# RangeHood.net
KiCad netlist of a schematic drawn in EAGLE
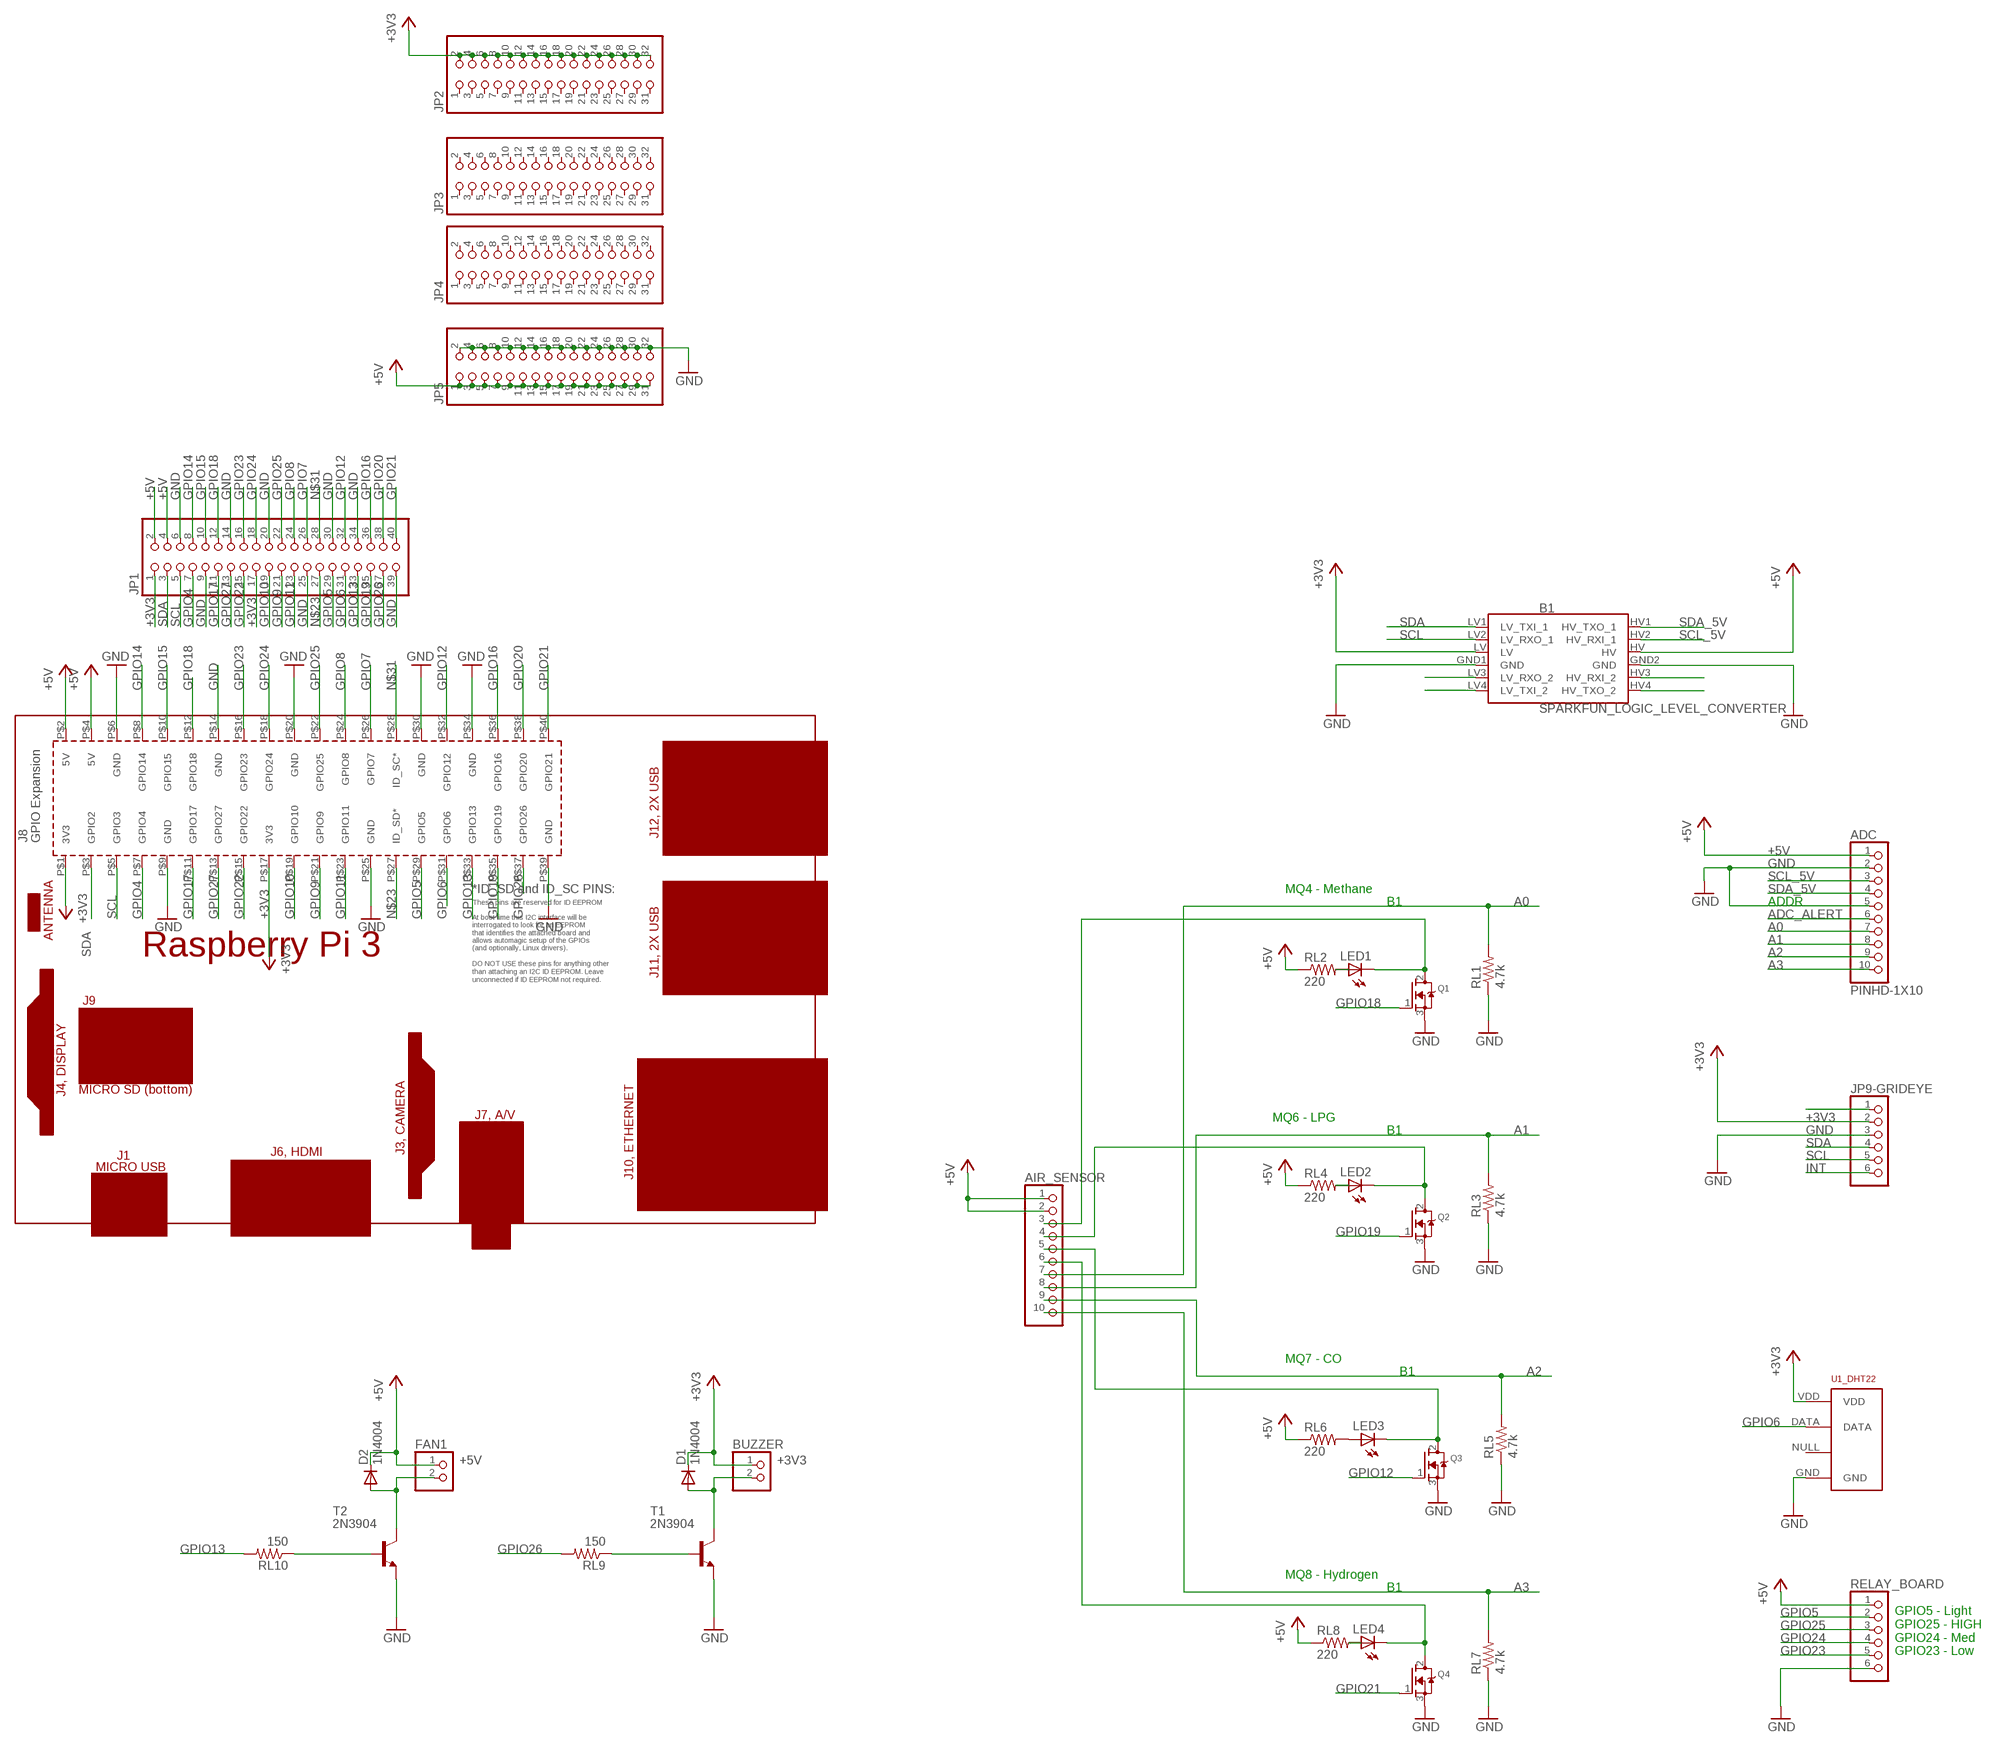
[diagram p0: schematic, sheet 1]

(export (version "E")
  (design (tool "Eeschema 10.0.6"))
  (components
    (comp (ref "ADC")
      (value "PINHD-1X10")
      (footprint "eagle-import:1X10-BIG")
      (libsource (lib "eagle-import") (part "PINHD-1X10"))
    )
    (comp (ref "AIR_SENSOR")
      (value "PINHD-1X10")
      (footprint "eagle-import:1X10")
      (libsource (lib "eagle-import") (part "pinhead_325_PINHD-1X10"))
    )
    (comp (ref "B1")
      (value "SPARKFUN_LOGIC_LEVEL_CONVERTER")
      (footprint "eagle-import:SPARKFUN_LOGIC_LEVEL_CONVERTER")
      (libsource (lib "eagle-import") (part "SPARKFUN_LOGIC_LEVEL_CONVERTER"))
    )
    (comp (ref "BUZZER")
      (value "PINHD-1X2")
      (footprint "eagle-import:1X02")
      (libsource (lib "eagle-import") (part "PINHD-1X2"))
    )
    (comp (ref "D1")
      (value "1N4004")
      (footprint "eagle-import:DO41-10")
      (libsource (lib "eagle-import") (part "1N4004"))
    )
    (comp (ref "D2")
      (value "1N4004")
      (footprint "eagle-import:DO41-10")
      (libsource (lib "eagle-import") (part "1N4004"))
    )
    (comp (ref "FAN1")
      (value "PINHD-1X2")
      (footprint "eagle-import:1X02")
      (libsource (lib "eagle-import") (part "PINHD-1X2"))
    )
    (comp (ref "JP1")
      (value "PINHD-2X20")
      (footprint "eagle-import:2X20")
      (libsource (lib "eagle-import") (part "PINHD-2X20"))
    )
    (comp (ref "JP2")
      (value "PINHD-2X16")
      (footprint "eagle-import:2X16")
      (libsource (lib "eagle-import") (part "PINHD-2X16"))
    )
    (comp (ref "JP3")
      (value "PINHD-2X16")
      (footprint "eagle-import:2X16")
      (libsource (lib "eagle-import") (part "PINHD-2X16"))
    )
    (comp (ref "JP4")
      (value "PINHD-2X16")
      (footprint "eagle-import:2X16")
      (libsource (lib "eagle-import") (part "PINHD-2X16"))
    )
    (comp (ref "JP5")
      (value "PINHD-2X16")
      (footprint "eagle-import:2X16")
      (libsource (lib "eagle-import") (part "PINHD-2X16"))
    )
    (comp (ref "JP9-GRIDEYE")
      (value "PINHD-1X6")
      (footprint "eagle-import:1X06")
      (libsource (lib "eagle-import") (part "PINHD-1X6"))
    )
    (comp (ref "LED1")
      (value "LED3MM")
      (footprint "eagle-import:LED3MM")
      (libsource (lib "eagle-import") (part "LED3MM"))
    )
    (comp (ref "LED2")
      (value "LED3MM")
      (footprint "eagle-import:LED3MM")
      (libsource (lib "eagle-import") (part "LED3MM"))
    )
    (comp (ref "LED3")
      (value "LED3MM")
      (footprint "eagle-import:LED3MM")
      (libsource (lib "eagle-import") (part "LED3MM"))
    )
    (comp (ref "LED4")
      (value "LED3MM")
      (footprint "eagle-import:LED3MM")
      (libsource (lib "eagle-import") (part "LED3MM"))
    )
    (comp (ref "PCB1")
      (value "RPI3")
      (footprint "eagle-import:RPI3")
      (libsource (lib "eagle-import") (part "RPI3"))
    )
    (comp (ref "Q1")
      (value "MOSFET-NGDS_TO220V")
      (footprint "eagle-import:TO220V")
      (libsource (lib "eagle-import") (part "MOSFET-NGDS_TO220V"))
    )
    (comp (ref "Q2")
      (value "MOSFET-NGDS_TO220V")
      (footprint "eagle-import:TO220V")
      (libsource (lib "eagle-import") (part "MOSFET-NGDS_TO220V"))
    )
    (comp (ref "Q3")
      (value "MOSFET-NGDS_TO220V")
      (footprint "eagle-import:TO220V")
      (libsource (lib "eagle-import") (part "MOSFET-NGDS_TO220V"))
    )
    (comp (ref "Q4")
      (value "MOSFET-NGDS_TO220V")
      (footprint "eagle-import:TO220V")
      (libsource (lib "eagle-import") (part "MOSFET-NGDS_TO220V"))
    )
    (comp (ref "RELAY_BOARD")
      (value "PINHD-1X6")
      (footprint "eagle-import:1X06")
      (libsource (lib "eagle-import") (part "PINHD-1X6"))
    )
    (comp (ref "RL1")
      (value "4.7k")
      (footprint "eagle-import:M0805")
      (libsource (lib "eagle-import") (part "R-US_M0805"))
    )
    (comp (ref "RL2")
      (value "220")
      (footprint "eagle-import:M0805")
      (libsource (lib "eagle-import") (part "R-US_M0805"))
    )
    (comp (ref "RL3")
      (value "4.7k")
      (footprint "eagle-import:M0805")
      (libsource (lib "eagle-import") (part "R-US_M0805"))
    )
    (comp (ref "RL4")
      (value "220")
      (footprint "eagle-import:M0805")
      (libsource (lib "eagle-import") (part "R-US_M0805"))
    )
    (comp (ref "RL5")
      (value "4.7k")
      (footprint "eagle-import:M0805")
      (libsource (lib "eagle-import") (part "R-US_M0805"))
    )
    (comp (ref "RL6")
      (value "220")
      (footprint "eagle-import:M0805")
      (libsource (lib "eagle-import") (part "R-US_M0805"))
    )
    (comp (ref "RL7")
      (value "4.7k")
      (footprint "eagle-import:M0805")
      (libsource (lib "eagle-import") (part "R-US_M0805"))
    )
    (comp (ref "RL8")
      (value "220")
      (footprint "eagle-import:M0805")
      (libsource (lib "eagle-import") (part "R-US_M0805"))
    )
    (comp (ref "RL9")
      (value "150")
      (footprint "eagle-import:M0805")
      (libsource (lib "eagle-import") (part "R-US_M0805"))
    )
    (comp (ref "RL10")
      (value "150")
      (footprint "eagle-import:M0805")
      (libsource (lib "eagle-import") (part "R-US_M0805"))
    )
    (comp (ref "T1")
      (value "2N3904")
      (footprint "eagle-import:TO92")
      (libsource (lib "eagle-import") (part "2N3904"))
    )
    (comp (ref "T2")
      (value "2N3904")
      (footprint "eagle-import:TO92")
      (libsource (lib "eagle-import") (part "2N3904"))
    )
    (comp (ref "U1_DHT22")
      (value "RHT03_DHT-22_AM2302")
      (footprint "eagle-import:RHT03_DHT-22")
      (libsource (lib "eagle-import") (part "RHT03_DHT-22_AM2302"))
    )
  )
  (nets
    (net (code "1") (name "+3V3") (class "Default")
      (node (ref "B1") (pin "LV") (pinfunction "LV_LV") (pintype "power_in"))
      (node (ref "BUZZER") (pin "1") (pinfunction "1_1") (pintype "passive"))
      (node (ref "D1") (pin "C") (pinfunction "C_C") (pintype "passive"))
      (node (ref "JP1") (pin "1") (pinfunction "1_1") (pintype "passive"))
      (node (ref "JP1") (pin "17") (pinfunction "17_17") (pintype "passive"))
      (node (ref "JP2") (pin "10") (pinfunction "10_10") (pintype "passive"))
      (node (ref "JP2") (pin "12") (pinfunction "12_12") (pintype "passive"))
      (node (ref "JP2") (pin "14") (pinfunction "14_14") (pintype "passive"))
      (node (ref "JP2") (pin "16") (pinfunction "16_16") (pintype "passive"))
      (node (ref "JP2") (pin "18") (pinfunction "18_18") (pintype "passive"))
      (node (ref "JP2") (pin "2") (pinfunction "2_2") (pintype "passive"))
      (node (ref "JP2") (pin "20") (pinfunction "20_20") (pintype "passive"))
      (node (ref "JP2") (pin "22") (pinfunction "22_22") (pintype "passive"))
      (node (ref "JP2") (pin "24") (pinfunction "24_24") (pintype "passive"))
      (node (ref "JP2") (pin "26") (pinfunction "26_26") (pintype "passive"))
      (node (ref "JP2") (pin "28") (pinfunction "28_28") (pintype "passive"))
      (node (ref "JP2") (pin "30") (pinfunction "30_30") (pintype "passive"))
      (node (ref "JP2") (pin "32") (pinfunction "32_32") (pintype "passive"))
      (node (ref "JP2") (pin "4") (pinfunction "4_4") (pintype "passive"))
      (node (ref "JP2") (pin "6") (pinfunction "6_6") (pintype "passive"))
      (node (ref "JP2") (pin "8") (pinfunction "8_8") (pintype "passive"))
      (node (ref "JP9-GRIDEYE") (pin "2") (pinfunction "2_2") (pintype "passive"))
      (node (ref "PCB1") (pin "P$1") (pinfunction "3V3_P$1") (pintype "bidirectional"))
      (node (ref "PCB1") (pin "P$17") (pinfunction "3V3_P$17") (pintype "bidirectional"))
      (node (ref "U1_DHT22") (pin "VDD") (pinfunction "VDD_VDD") (pintype "power_in"))
    )
    (net (code "2") (name "+5V") (class "Default")
      (node (ref "ADC") (pin "1") (pinfunction "1_1") (pintype "passive"))
      (node (ref "AIR_SENSOR") (pin "1") (pinfunction "1_1") (pintype "passive"))
      (node (ref "AIR_SENSOR") (pin "2") (pinfunction "2_2") (pintype "passive"))
      (node (ref "B1") (pin "HV") (pinfunction "HV_HV") (pintype "power_in"))
      (node (ref "D2") (pin "C") (pinfunction "C_C") (pintype "passive"))
      (node (ref "FAN1") (pin "1") (pinfunction "1_1") (pintype "passive"))
      (node (ref "JP1") (pin "2") (pinfunction "2_2") (pintype "passive"))
      (node (ref "JP1") (pin "4") (pinfunction "4_4") (pintype "passive"))
      (node (ref "JP5") (pin "1") (pinfunction "1_1") (pintype "passive"))
      (node (ref "JP5") (pin "11") (pinfunction "11_11") (pintype "passive"))
      (node (ref "JP5") (pin "13") (pinfunction "13_13") (pintype "passive"))
      (node (ref "JP5") (pin "15") (pinfunction "15_15") (pintype "passive"))
      (node (ref "JP5") (pin "17") (pinfunction "17_17") (pintype "passive"))
      (node (ref "JP5") (pin "19") (pinfunction "19_19") (pintype "passive"))
      (node (ref "JP5") (pin "21") (pinfunction "21_21") (pintype "passive"))
      (node (ref "JP5") (pin "23") (pinfunction "23_23") (pintype "passive"))
      (node (ref "JP5") (pin "25") (pinfunction "25_25") (pintype "passive"))
      (node (ref "JP5") (pin "27") (pinfunction "27_27") (pintype "passive"))
      (node (ref "JP5") (pin "29") (pinfunction "29_29") (pintype "passive"))
      (node (ref "JP5") (pin "3") (pinfunction "3_3") (pintype "passive"))
      (node (ref "JP5") (pin "31") (pinfunction "31_31") (pintype "passive"))
      (node (ref "JP5") (pin "5") (pinfunction "5_5") (pintype "passive"))
      (node (ref "JP5") (pin "7") (pinfunction "7_7") (pintype "passive"))
      (node (ref "JP5") (pin "9") (pinfunction "9_9") (pintype "passive"))
      (node (ref "PCB1") (pin "P$2") (pinfunction "5V_P$2") (pintype "bidirectional"))
      (node (ref "PCB1") (pin "P$4") (pinfunction "5V_P$4") (pintype "bidirectional"))
      (node (ref "RELAY_BOARD") (pin "1") (pinfunction "1_1") (pintype "passive"))
      (node (ref "RL2") (pin "1") (pinfunction "1_1") (pintype "passive"))
      (node (ref "RL4") (pin "1") (pinfunction "1_1") (pintype "passive"))
      (node (ref "RL6") (pin "1") (pinfunction "1_1") (pintype "passive"))
      (node (ref "RL8") (pin "1") (pinfunction "1_1") (pintype "passive"))
    )
    (net (code "3") (name "A0") (class "Default")
      (node (ref "ADC") (pin "7") (pinfunction "7_7") (pintype "passive"))
      (node (ref "AIR_SENSOR") (pin "7") (pinfunction "7_7") (pintype "passive"))
      (node (ref "RL1") (pin "2") (pinfunction "2_2") (pintype "passive"))
    )
    (net (code "4") (name "A1") (class "Default")
      (node (ref "ADC") (pin "8") (pinfunction "8_8") (pintype "passive"))
      (node (ref "AIR_SENSOR") (pin "8") (pinfunction "8_8") (pintype "passive"))
      (node (ref "RL3") (pin "2") (pinfunction "2_2") (pintype "passive"))
    )
    (net (code "5") (name "A2") (class "Default")
      (node (ref "ADC") (pin "9") (pinfunction "9_9") (pintype "passive"))
      (node (ref "AIR_SENSOR") (pin "9") (pinfunction "9_9") (pintype "passive"))
      (node (ref "RL5") (pin "2") (pinfunction "2_2") (pintype "passive"))
    )
    (net (code "6") (name "A3") (class "Default")
      (node (ref "ADC") (pin "10") (pinfunction "10_10") (pintype "passive"))
      (node (ref "AIR_SENSOR") (pin "10") (pinfunction "10_10") (pintype "passive"))
      (node (ref "RL7") (pin "2") (pinfunction "2_2") (pintype "passive"))
    )
    (net (code "7") (name "ADC_ALERT") (class "Default")
      (node (ref "ADC") (pin "6") (pinfunction "6_6") (pintype "passive"))
    )
    (net (code "8") (name "GND") (class "Default")
      (node (ref "ADC") (pin "2") (pinfunction "2_2") (pintype "passive"))
      (node (ref "ADC") (pin "5") (pinfunction "5_5") (pintype "passive"))
      (node (ref "B1") (pin "GND1") (pinfunction "GND_GND1") (pintype "power_in"))
      (node (ref "B1") (pin "GND2") (pinfunction "GND_GND2") (pintype "power_in"))
      (node (ref "JP1") (pin "14") (pinfunction "14_14") (pintype "passive"))
      (node (ref "JP1") (pin "20") (pinfunction "20_20") (pintype "passive"))
      (node (ref "JP1") (pin "25") (pinfunction "25_25") (pintype "passive"))
      (node (ref "JP1") (pin "30") (pinfunction "30_30") (pintype "passive"))
      (node (ref "JP1") (pin "34") (pinfunction "34_34") (pintype "passive"))
      (node (ref "JP1") (pin "39") (pinfunction "39_39") (pintype "passive"))
      (node (ref "JP1") (pin "6") (pinfunction "6_6") (pintype "passive"))
      (node (ref "JP1") (pin "9") (pinfunction "9_9") (pintype "passive"))
      (node (ref "JP5") (pin "10") (pinfunction "10_10") (pintype "passive"))
      (node (ref "JP5") (pin "12") (pinfunction "12_12") (pintype "passive"))
      (node (ref "JP5") (pin "14") (pinfunction "14_14") (pintype "passive"))
      (node (ref "JP5") (pin "16") (pinfunction "16_16") (pintype "passive"))
      (node (ref "JP5") (pin "18") (pinfunction "18_18") (pintype "passive"))
      (node (ref "JP5") (pin "2") (pinfunction "2_2") (pintype "passive"))
      (node (ref "JP5") (pin "20") (pinfunction "20_20") (pintype "passive"))
      (node (ref "JP5") (pin "22") (pinfunction "22_22") (pintype "passive"))
      (node (ref "JP5") (pin "24") (pinfunction "24_24") (pintype "passive"))
      (node (ref "JP5") (pin "26") (pinfunction "26_26") (pintype "passive"))
      (node (ref "JP5") (pin "28") (pinfunction "28_28") (pintype "passive"))
      (node (ref "JP5") (pin "30") (pinfunction "30_30") (pintype "passive"))
      (node (ref "JP5") (pin "32") (pinfunction "32_32") (pintype "passive"))
      (node (ref "JP5") (pin "4") (pinfunction "4_4") (pintype "passive"))
      (node (ref "JP5") (pin "6") (pinfunction "6_6") (pintype "passive"))
      (node (ref "JP5") (pin "8") (pinfunction "8_8") (pintype "passive"))
      (node (ref "JP9-GRIDEYE") (pin "3") (pinfunction "3_3") (pintype "passive"))
      (node (ref "PCB1") (pin "P$14") (pinfunction "GND_P$14") (pintype "bidirectional"))
      (node (ref "PCB1") (pin "P$20") (pinfunction "GND_P$20") (pintype "bidirectional"))
      (node (ref "PCB1") (pin "P$25") (pinfunction "GND_P$25") (pintype "bidirectional"))
      (node (ref "PCB1") (pin "P$30") (pinfunction "GND_P$30") (pintype "bidirectional"))
      (node (ref "PCB1") (pin "P$34") (pinfunction "GND_P$34") (pintype "bidirectional"))
      (node (ref "PCB1") (pin "P$39") (pinfunction "GND_P$39") (pintype "bidirectional"))
      (node (ref "PCB1") (pin "P$6") (pinfunction "GND_P$6") (pintype "bidirectional"))
      (node (ref "PCB1") (pin "P$9") (pinfunction "GND_P$9") (pintype "bidirectional"))
      (node (ref "Q1") (pin "3") (pinfunction "S_3") (pintype "bidirectional"))
      (node (ref "Q2") (pin "3") (pinfunction "S_3") (pintype "bidirectional"))
      (node (ref "Q3") (pin "3") (pinfunction "S_3") (pintype "bidirectional"))
      (node (ref "Q4") (pin "3") (pinfunction "S_3") (pintype "bidirectional"))
      (node (ref "RELAY_BOARD") (pin "6") (pinfunction "6_6") (pintype "passive"))
      (node (ref "RL1") (pin "1") (pinfunction "1_1") (pintype "passive"))
      (node (ref "RL3") (pin "1") (pinfunction "1_1") (pintype "passive"))
      (node (ref "RL5") (pin "1") (pinfunction "1_1") (pintype "passive"))
      (node (ref "RL7") (pin "1") (pinfunction "1_1") (pintype "passive"))
      (node (ref "T1") (pin "3") (pinfunction "E_3") (pintype "passive"))
      (node (ref "T2") (pin "3") (pinfunction "E_3") (pintype "passive"))
      (node (ref "U1_DHT22") (pin "GND") (pinfunction "GND_GND") (pintype "power_in"))
    )
    (net (code "9") (name "GPIO4") (class "Default")
      (node (ref "JP1") (pin "7") (pinfunction "7_7") (pintype "passive"))
      (node (ref "PCB1") (pin "P$7") (pinfunction "GPIO4_P$7") (pintype "bidirectional"))
    )
    (net (code "10") (name "GPIO5") (class "Default")
      (node (ref "JP1") (pin "29") (pinfunction "29_29") (pintype "passive"))
      (node (ref "PCB1") (pin "P$29") (pinfunction "GPIO5_P$29") (pintype "bidirectional"))
      (node (ref "RELAY_BOARD") (pin "2") (pinfunction "2_2") (pintype "passive"))
    )
    (net (code "11") (name "GPIO6") (class "Default")
      (node (ref "JP1") (pin "31") (pinfunction "31_31") (pintype "passive"))
      (node (ref "PCB1") (pin "P$31") (pinfunction "GPIO6_P$31") (pintype "bidirectional"))
      (node (ref "U1_DHT22") (pin "DATA") (pinfunction "DATA_DATA") (pintype "bidirectional"))
    )
    (net (code "12") (name "GPIO7") (class "Default")
      (node (ref "JP1") (pin "26") (pinfunction "26_26") (pintype "passive"))
      (node (ref "PCB1") (pin "P$26") (pinfunction "GPIO7_P$26") (pintype "bidirectional"))
    )
    (net (code "13") (name "GPIO8") (class "Default")
      (node (ref "JP1") (pin "24") (pinfunction "24_24") (pintype "passive"))
      (node (ref "PCB1") (pin "P$24") (pinfunction "GPIO8_P$24") (pintype "bidirectional"))
    )
    (net (code "14") (name "GPIO9") (class "Default")
      (node (ref "JP1") (pin "21") (pinfunction "21_21") (pintype "passive"))
      (node (ref "PCB1") (pin "P$21") (pinfunction "GPIO9_P$21") (pintype "bidirectional"))
    )
    (net (code "15") (name "GPIO10") (class "Default")
      (node (ref "JP1") (pin "19") (pinfunction "19_19") (pintype "passive"))
      (node (ref "PCB1") (pin "P$19") (pinfunction "GPIO10_P$19") (pintype "bidirectional"))
    )
    (net (code "16") (name "GPIO11") (class "Default")
      (node (ref "JP1") (pin "23") (pinfunction "23_23") (pintype "passive"))
      (node (ref "PCB1") (pin "P$23") (pinfunction "GPIO11_P$23") (pintype "bidirectional"))
    )
    (net (code "17") (name "GPIO12") (class "Default")
      (node (ref "JP1") (pin "32") (pinfunction "32_32") (pintype "passive"))
      (node (ref "PCB1") (pin "P$32") (pinfunction "GPIO12_P$32") (pintype "bidirectional"))
      (node (ref "Q3") (pin "1") (pinfunction "G_1") (pintype "bidirectional"))
    )
    (net (code "18") (name "GPIO13") (class "Default")
      (node (ref "JP1") (pin "33") (pinfunction "33_33") (pintype "passive"))
      (node (ref "PCB1") (pin "P$33") (pinfunction "GPIO13_P$33") (pintype "bidirectional"))
      (node (ref "RL10") (pin "2") (pinfunction "2_2") (pintype "passive"))
    )
    (net (code "19") (name "GPIO14") (class "Default")
      (node (ref "JP1") (pin "8") (pinfunction "8_8") (pintype "passive"))
      (node (ref "PCB1") (pin "P$8") (pinfunction "GPIO14_P$8") (pintype "bidirectional"))
    )
    (net (code "20") (name "GPIO15") (class "Default")
      (node (ref "JP1") (pin "10") (pinfunction "10_10") (pintype "passive"))
      (node (ref "PCB1") (pin "P$10") (pinfunction "GPIO15_P$10") (pintype "bidirectional"))
    )
    (net (code "21") (name "GPIO16") (class "Default")
      (node (ref "JP1") (pin "36") (pinfunction "36_36") (pintype "passive"))
      (node (ref "PCB1") (pin "P$36") (pinfunction "GPIO16_P$36") (pintype "bidirectional"))
    )
    (net (code "22") (name "GPIO17") (class "Default")
      (node (ref "JP1") (pin "11") (pinfunction "11_11") (pintype "passive"))
      (node (ref "PCB1") (pin "P$11") (pinfunction "GPIO17_P$11") (pintype "bidirectional"))
    )
    (net (code "23") (name "GPIO18") (class "Default")
      (node (ref "JP1") (pin "12") (pinfunction "12_12") (pintype "passive"))
      (node (ref "PCB1") (pin "P$12") (pinfunction "GPIO18_P$12") (pintype "bidirectional"))
      (node (ref "Q1") (pin "1") (pinfunction "G_1") (pintype "bidirectional"))
    )
    (net (code "24") (name "GPIO19") (class "Default")
      (node (ref "JP1") (pin "35") (pinfunction "35_35") (pintype "passive"))
      (node (ref "PCB1") (pin "P$35") (pinfunction "GPIO19_P$35") (pintype "bidirectional"))
      (node (ref "Q2") (pin "1") (pinfunction "G_1") (pintype "bidirectional"))
    )
    (net (code "25") (name "GPIO20") (class "Default")
      (node (ref "JP1") (pin "38") (pinfunction "38_38") (pintype "passive"))
      (node (ref "PCB1") (pin "P$38") (pinfunction "GPIO20_P$38") (pintype "bidirectional"))
    )
    (net (code "26") (name "GPIO21") (class "Default")
      (node (ref "JP1") (pin "40") (pinfunction "40_40") (pintype "passive"))
      (node (ref "PCB1") (pin "P$40") (pinfunction "GPIO21_P$40") (pintype "bidirectional"))
      (node (ref "Q4") (pin "1") (pinfunction "G_1") (pintype "bidirectional"))
    )
    (net (code "27") (name "GPIO22") (class "Default")
      (node (ref "JP1") (pin "15") (pinfunction "15_15") (pintype "passive"))
      (node (ref "PCB1") (pin "P$15") (pinfunction "GPIO22_P$15") (pintype "bidirectional"))
    )
    (net (code "28") (name "GPIO23") (class "Default")
      (node (ref "JP1") (pin "16") (pinfunction "16_16") (pintype "passive"))
      (node (ref "PCB1") (pin "P$16") (pinfunction "GPIO23_P$16") (pintype "bidirectional"))
      (node (ref "RELAY_BOARD") (pin "5") (pinfunction "5_5") (pintype "passive"))
    )
    (net (code "29") (name "GPIO24") (class "Default")
      (node (ref "JP1") (pin "18") (pinfunction "18_18") (pintype "passive"))
      (node (ref "PCB1") (pin "P$18") (pinfunction "GPIO24_P$18") (pintype "bidirectional"))
      (node (ref "RELAY_BOARD") (pin "4") (pinfunction "4_4") (pintype "passive"))
    )
    (net (code "30") (name "GPIO25") (class "Default")
      (node (ref "JP1") (pin "22") (pinfunction "22_22") (pintype "passive"))
      (node (ref "PCB1") (pin "P$22") (pinfunction "GPIO25_P$22") (pintype "bidirectional"))
      (node (ref "RELAY_BOARD") (pin "3") (pinfunction "3_3") (pintype "passive"))
    )
    (net (code "31") (name "GPIO26") (class "Default")
      (node (ref "JP1") (pin "37") (pinfunction "37_37") (pintype "passive"))
      (node (ref "PCB1") (pin "P$37") (pinfunction "GPIO26_P$37") (pintype "bidirectional"))
      (node (ref "RL9") (pin "2") (pinfunction "2_2") (pintype "passive"))
    )
    (net (code "32") (name "GPIO27") (class "Default")
      (node (ref "JP1") (pin "13") (pinfunction "13_13") (pintype "passive"))
      (node (ref "PCB1") (pin "P$13") (pinfunction "GPIO27_P$13") (pintype "bidirectional"))
    )
    (net (code "33") (name "INT") (class "Default")
      (node (ref "JP9-GRIDEYE") (pin "6") (pinfunction "6_6") (pintype "passive"))
    )
    (net (code "34") (name "N$23") (class "Default")
      (node (ref "JP1") (pin "27") (pinfunction "27_27") (pintype "passive"))
      (node (ref "PCB1") (pin "P$27") (pinfunction "ID_SD*_P$27") (pintype "bidirectional"))
    )
    (net (code "35") (name "N$31") (class "Default")
      (node (ref "JP1") (pin "28") (pinfunction "28_28") (pintype "passive"))
      (node (ref "PCB1") (pin "P$28") (pinfunction "ID_SC*_P$28") (pintype "bidirectional"))
    )
    (net (code "36") (name "Net-(LED1-C)") (class "Default")
      (node (ref "AIR_SENSOR") (pin "3") (pinfunction "3_3") (pintype "passive"))
      (node (ref "LED1") (pin "K") (pinfunction "C_K") (pintype "passive"))
      (node (ref "Q1") (pin "2") (pinfunction "D_2") (pintype "bidirectional"))
    )
    (net (code "37") (name "Net-(LED1-PadA)") (class "Default")
      (node (ref "LED1") (pin "A") (pinfunction "A_A") (pintype "passive"))
      (node (ref "RL2") (pin "2") (pinfunction "2_2") (pintype "passive"))
    )
    (net (code "38") (name "Net-(LED2-C)") (class "Default")
      (node (ref "AIR_SENSOR") (pin "4") (pinfunction "4_4") (pintype "passive"))
      (node (ref "LED2") (pin "K") (pinfunction "C_K") (pintype "passive"))
      (node (ref "Q2") (pin "2") (pinfunction "D_2") (pintype "bidirectional"))
    )
    (net (code "39") (name "Net-(LED2-PadA)") (class "Default")
      (node (ref "LED2") (pin "A") (pinfunction "A_A") (pintype "passive"))
      (node (ref "RL4") (pin "2") (pinfunction "2_2") (pintype "passive"))
    )
    (net (code "40") (name "Net-(LED3-C)") (class "Default")
      (node (ref "AIR_SENSOR") (pin "5") (pinfunction "5_5") (pintype "passive"))
      (node (ref "LED3") (pin "K") (pinfunction "C_K") (pintype "passive"))
      (node (ref "Q3") (pin "2") (pinfunction "D_2") (pintype "bidirectional"))
    )
    (net (code "41") (name "Net-(LED3-PadA)") (class "Default")
      (node (ref "LED3") (pin "A") (pinfunction "A_A") (pintype "passive"))
      (node (ref "RL6") (pin "2") (pinfunction "2_2") (pintype "passive"))
    )
    (net (code "42") (name "Net-(LED4-C)") (class "Default")
      (node (ref "AIR_SENSOR") (pin "6") (pinfunction "6_6") (pintype "passive"))
      (node (ref "LED4") (pin "K") (pinfunction "C_K") (pintype "passive"))
      (node (ref "Q4") (pin "2") (pinfunction "D_2") (pintype "bidirectional"))
    )
    (net (code "43") (name "Net-(LED4-PadA)") (class "Default")
      (node (ref "LED4") (pin "A") (pinfunction "A_A") (pintype "passive"))
      (node (ref "RL8") (pin "2") (pinfunction "2_2") (pintype "passive"))
    )
    (net (code "44") (name "Net-(T1-B)") (class "Default")
      (node (ref "RL9") (pin "1") (pinfunction "1_1") (pintype "passive"))
      (node (ref "T1") (pin "2") (pinfunction "B_2") (pintype "passive"))
    )
    (net (code "45") (name "Net-(T1-C)") (class "Default")
      (node (ref "BUZZER") (pin "2") (pinfunction "2_2") (pintype "passive"))
      (node (ref "D1") (pin "A") (pinfunction "A_A") (pintype "passive"))
      (node (ref "T1") (pin "1") (pinfunction "C_1") (pintype "passive"))
    )
    (net (code "46") (name "Net-(T2-B)") (class "Default")
      (node (ref "RL10") (pin "1") (pinfunction "1_1") (pintype "passive"))
      (node (ref "T2") (pin "2") (pinfunction "B_2") (pintype "passive"))
    )
    (net (code "47") (name "Net-(T2-C)") (class "Default")
      (node (ref "D2") (pin "A") (pinfunction "A_A") (pintype "passive"))
      (node (ref "FAN1") (pin "2") (pinfunction "2_2") (pintype "passive"))
      (node (ref "T2") (pin "1") (pinfunction "C_1") (pintype "passive"))
    )
    (net (code "48") (name "SCL") (class "Default")
      (node (ref "B1") (pin "LV2") (pinfunction "LV_RXO_1_LV2") (pintype "bidirectional"))
      (node (ref "JP1") (pin "5") (pinfunction "5_5") (pintype "passive"))
      (node (ref "JP9-GRIDEYE") (pin "5") (pinfunction "5_5") (pintype "passive"))
      (node (ref "PCB1") (pin "P$5") (pinfunction "GPIO3_P$5") (pintype "bidirectional"))
    )
    (net (code "49") (name "SCL_5V") (class "Default")
      (node (ref "ADC") (pin "3") (pinfunction "3_3") (pintype "passive"))
      (node (ref "B1") (pin "HV2") (pinfunction "HV_RXI_1_HV2") (pintype "bidirectional"))
    )
    (net (code "50") (name "SDA") (class "Default")
      (node (ref "B1") (pin "LV1") (pinfunction "LV_TXI_1_LV1") (pintype "bidirectional"))
      (node (ref "JP1") (pin "3") (pinfunction "3_3") (pintype "passive"))
      (node (ref "JP9-GRIDEYE") (pin "4") (pinfunction "4_4") (pintype "passive"))
      (node (ref "PCB1") (pin "P$3") (pinfunction "GPIO2_P$3") (pintype "bidirectional"))
    )
    (net (code "51") (name "SDA_5V") (class "Default")
      (node (ref "ADC") (pin "4") (pinfunction "4_4") (pintype "passive"))
      (node (ref "B1") (pin "HV1") (pinfunction "HV_TXO_1_HV1") (pintype "bidirectional"))
    )
    (net (code "52") (name "unconnected-(B1-HV_RXI_2-PadHV3)") (class "Default")
      (node (ref "B1") (pin "HV3") (pinfunction "HV_RXI_2_HV3") (pintype "bidirectional"))
    )
    (net (code "53") (name "unconnected-(B1-HV_TXO_2-PadHV4)") (class "Default")
      (node (ref "B1") (pin "HV4") (pinfunction "HV_TXO_2_HV4") (pintype "bidirectional"))
    )
    (net (code "54") (name "unconnected-(B1-LV_RXO_2-PadLV3)") (class "Default")
      (node (ref "B1") (pin "LV3") (pinfunction "LV_RXO_2_LV3") (pintype "bidirectional"))
    )
    (net (code "55") (name "unconnected-(B1-LV_TXI_2-PadLV4)") (class "Default")
      (node (ref "B1") (pin "LV4") (pinfunction "LV_TXI_2_LV4") (pintype "bidirectional"))
    )
    (net (code "56") (name "unconnected-(JP2-Pad1)") (class "Default")
      (node (ref "JP2") (pin "1") (pinfunction "1_1") (pintype "passive"))
    )
    (net (code "57") (name "unconnected-(JP2-Pad3)") (class "Default")
      (node (ref "JP2") (pin "3") (pinfunction "3_3") (pintype "passive"))
    )
    (net (code "58") (name "unconnected-(JP2-Pad5)") (class "Default")
      (node (ref "JP2") (pin "5") (pinfunction "5_5") (pintype "passive"))
    )
    (net (code "59") (name "unconnected-(JP2-Pad7)") (class "Default")
      (node (ref "JP2") (pin "7") (pinfunction "7_7") (pintype "passive"))
    )
    (net (code "60") (name "unconnected-(JP2-Pad9)") (class "Default")
      (node (ref "JP2") (pin "9") (pinfunction "9_9") (pintype "passive"))
    )
    (net (code "61") (name "unconnected-(JP2-Pad11)") (class "Default")
      (node (ref "JP2") (pin "11") (pinfunction "11_11") (pintype "passive"))
    )
    (net (code "62") (name "unconnected-(JP2-Pad13)") (class "Default")
      (node (ref "JP2") (pin "13") (pinfunction "13_13") (pintype "passive"))
    )
    (net (code "63") (name "unconnected-(JP2-Pad15)") (class "Default")
      (node (ref "JP2") (pin "15") (pinfunction "15_15") (pintype "passive"))
    )
    (net (code "64") (name "unconnected-(JP2-Pad17)") (class "Default")
      (node (ref "JP2") (pin "17") (pinfunction "17_17") (pintype "passive"))
    )
    (net (code "65") (name "unconnected-(JP2-Pad19)") (class "Default")
      (node (ref "JP2") (pin "19") (pinfunction "19_19") (pintype "passive"))
    )
    (net (code "66") (name "unconnected-(JP2-Pad21)") (class "Default")
      (node (ref "JP2") (pin "21") (pinfunction "21_21") (pintype "passive"))
    )
    (net (code "67") (name "unconnected-(JP2-Pad23)") (class "Default")
      (node (ref "JP2") (pin "23") (pinfunction "23_23") (pintype "passive"))
    )
    (net (code "68") (name "unconnected-(JP2-Pad25)") (class "Default")
      (node (ref "JP2") (pin "25") (pinfunction "25_25") (pintype "passive"))
    )
    (net (code "69") (name "unconnected-(JP2-Pad27)") (class "Default")
      (node (ref "JP2") (pin "27") (pinfunction "27_27") (pintype "passive"))
    )
    (net (code "70") (name "unconnected-(JP2-Pad29)") (class "Default")
      (node (ref "JP2") (pin "29") (pinfunction "29_29") (pintype "passive"))
    )
    (net (code "71") (name "unconnected-(JP2-Pad31)") (class "Default")
      (node (ref "JP2") (pin "31") (pinfunction "31_31") (pintype "passive"))
    )
    (net (code "72") (name "unconnected-(JP3-Pad1)") (class "Default")
      (node (ref "JP3") (pin "1") (pinfunction "1_1") (pintype "passive"))
    )
    (net (code "73") (name "unconnected-(JP3-Pad2)") (class "Default")
      (node (ref "JP3") (pin "2") (pinfunction "2_2") (pintype "passive"))
    )
    (net (code "74") (name "unconnected-(JP3-Pad3)") (class "Default")
      (node (ref "JP3") (pin "3") (pinfunction "3_3") (pintype "passive"))
    )
    (net (code "75") (name "unconnected-(JP3-Pad4)") (class "Default")
      (node (ref "JP3") (pin "4") (pinfunction "4_4") (pintype "passive"))
    )
    (net (code "76") (name "unconnected-(JP3-Pad5)") (class "Default")
      (node (ref "JP3") (pin "5") (pinfunction "5_5") (pintype "passive"))
    )
    (net (code "77") (name "unconnected-(JP3-Pad6)") (class "Default")
      (node (ref "JP3") (pin "6") (pinfunction "6_6") (pintype "passive"))
    )
    (net (code "78") (name "unconnected-(JP3-Pad7)") (class "Default")
      (node (ref "JP3") (pin "7") (pinfunction "7_7") (pintype "passive"))
    )
    (net (code "79") (name "unconnected-(JP3-Pad8)") (class "Default")
      (node (ref "JP3") (pin "8") (pinfunction "8_8") (pintype "passive"))
    )
    (net (code "80") (name "unconnected-(JP3-Pad9)") (class "Default")
      (node (ref "JP3") (pin "9") (pinfunction "9_9") (pintype "passive"))
    )
    (net (code "81") (name "unconnected-(JP3-Pad10)") (class "Default")
      (node (ref "JP3") (pin "10") (pinfunction "10_10") (pintype "passive"))
    )
    (net (code "82") (name "unconnected-(JP3-Pad11)") (class "Default")
      (node (ref "JP3") (pin "11") (pinfunction "11_11") (pintype "passive"))
    )
    (net (code "83") (name "unconnected-(JP3-Pad12)") (class "Default")
      (node (ref "JP3") (pin "12") (pinfunction "12_12") (pintype "passive"))
    )
    (net (code "84") (name "unconnected-(JP3-Pad13)") (class "Default")
      (node (ref "JP3") (pin "13") (pinfunction "13_13") (pintype "passive"))
    )
    (net (code "85") (name "unconnected-(JP3-Pad14)") (class "Default")
      (node (ref "JP3") (pin "14") (pinfunction "14_14") (pintype "passive"))
    )
    (net (code "86") (name "unconnected-(JP3-Pad15)") (class "Default")
      (node (ref "JP3") (pin "15") (pinfunction "15_15") (pintype "passive"))
    )
    (net (code "87") (name "unconnected-(JP3-Pad16)") (class "Default")
      (node (ref "JP3") (pin "16") (pinfunction "16_16") (pintype "passive"))
    )
    (net (code "88") (name "unconnected-(JP3-Pad17)") (class "Default")
      (node (ref "JP3") (pin "17") (pinfunction "17_17") (pintype "passive"))
    )
    (net (code "89") (name "unconnected-(JP3-Pad18)") (class "Default")
      (node (ref "JP3") (pin "18") (pinfunction "18_18") (pintype "passive"))
    )
    (net (code "90") (name "unconnected-(JP3-Pad19)") (class "Default")
      (node (ref "JP3") (pin "19") (pinfunction "19_19") (pintype "passive"))
    )
    (net (code "91") (name "unconnected-(JP3-Pad20)") (class "Default")
      (node (ref "JP3") (pin "20") (pinfunction "20_20") (pintype "passive"))
    )
    (net (code "92") (name "unconnected-(JP3-Pad21)") (class "Default")
      (node (ref "JP3") (pin "21") (pinfunction "21_21") (pintype "passive"))
    )
    (net (code "93") (name "unconnected-(JP3-Pad22)") (class "Default")
      (node (ref "JP3") (pin "22") (pinfunction "22_22") (pintype "passive"))
    )
    (net (code "94") (name "unconnected-(JP3-Pad23)") (class "Default")
      (node (ref "JP3") (pin "23") (pinfunction "23_23") (pintype "passive"))
    )
    (net (code "95") (name "unconnected-(JP3-Pad24)") (class "Default")
      (node (ref "JP3") (pin "24") (pinfunction "24_24") (pintype "passive"))
    )
    (net (code "96") (name "unconnected-(JP3-Pad25)") (class "Default")
      (node (ref "JP3") (pin "25") (pinfunction "25_25") (pintype "passive"))
    )
    (net (code "97") (name "unconnected-(JP3-Pad26)") (class "Default")
      (node (ref "JP3") (pin "26") (pinfunction "26_26") (pintype "passive"))
    )
    (net (code "98") (name "unconnected-(JP3-Pad27)") (class "Default")
      (node (ref "JP3") (pin "27") (pinfunction "27_27") (pintype "passive"))
    )
    (net (code "99") (name "unconnected-(JP3-Pad28)") (class "Default")
      (node (ref "JP3") (pin "28") (pinfunction "28_28") (pintype "passive"))
    )
    (net (code "100") (name "unconnected-(JP3-Pad29)") (class "Default")
      (node (ref "JP3") (pin "29") (pinfunction "29_29") (pintype "passive"))
    )
    (net (code "101") (name "unconnected-(JP3-Pad30)") (class "Default")
      (node (ref "JP3") (pin "30") (pinfunction "30_30") (pintype "passive"))
    )
    (net (code "102") (name "unconnected-(JP3-Pad31)") (class "Default")
      (node (ref "JP3") (pin "31") (pinfunction "31_31") (pintype "passive"))
    )
    (net (code "103") (name "unconnected-(JP3-Pad32)") (class "Default")
      (node (ref "JP3") (pin "32") (pinfunction "32_32") (pintype "passive"))
    )
    (net (code "104") (name "unconnected-(JP4-Pad1)") (class "Default")
      (node (ref "JP4") (pin "1") (pinfunction "1_1") (pintype "passive"))
    )
    (net (code "105") (name "unconnected-(JP4-Pad2)") (class "Default")
      (node (ref "JP4") (pin "2") (pinfunction "2_2") (pintype "passive"))
    )
    (net (code "106") (name "unconnected-(JP4-Pad3)") (class "Default")
      (node (ref "JP4") (pin "3") (pinfunction "3_3") (pintype "passive"))
    )
    (net (code "107") (name "unconnected-(JP4-Pad4)") (class "Default")
      (node (ref "JP4") (pin "4") (pinfunction "4_4") (pintype "passive"))
    )
    (net (code "108") (name "unconnected-(JP4-Pad5)") (class "Default")
      (node (ref "JP4") (pin "5") (pinfunction "5_5") (pintype "passive"))
    )
    (net (code "109") (name "unconnected-(JP4-Pad6)") (class "Default")
      (node (ref "JP4") (pin "6") (pinfunction "6_6") (pintype "passive"))
    )
    (net (code "110") (name "unconnected-(JP4-Pad7)") (class "Default")
      (node (ref "JP4") (pin "7") (pinfunction "7_7") (pintype "passive"))
    )
    (net (code "111") (name "unconnected-(JP4-Pad8)") (class "Default")
      (node (ref "JP4") (pin "8") (pinfunction "8_8") (pintype "passive"))
    )
    (net (code "112") (name "unconnected-(JP4-Pad9)") (class "Default")
      (node (ref "JP4") (pin "9") (pinfunction "9_9") (pintype "passive"))
    )
    (net (code "113") (name "unconnected-(JP4-Pad10)") (class "Default")
      (node (ref "JP4") (pin "10") (pinfunction "10_10") (pintype "passive"))
    )
    (net (code "114") (name "unconnected-(JP4-Pad11)") (class "Default")
      (node (ref "JP4") (pin "11") (pinfunction "11_11") (pintype "passive"))
    )
    (net (code "115") (name "unconnected-(JP4-Pad12)") (class "Default")
      (node (ref "JP4") (pin "12") (pinfunction "12_12") (pintype "passive"))
    )
    (net (code "116") (name "unconnected-(JP4-Pad13)") (class "Default")
      (node (ref "JP4") (pin "13") (pinfunction "13_13") (pintype "passive"))
    )
    (net (code "117") (name "unconnected-(JP4-Pad14)") (class "Default")
      (node (ref "JP4") (pin "14") (pinfunction "14_14") (pintype "passive"))
    )
    (net (code "118") (name "unconnected-(JP4-Pad15)") (class "Default")
      (node (ref "JP4") (pin "15") (pinfunction "15_15") (pintype "passive"))
    )
    (net (code "119") (name "unconnected-(JP4-Pad16)") (class "Default")
      (node (ref "JP4") (pin "16") (pinfunction "16_16") (pintype "passive"))
    )
    (net (code "120") (name "unconnected-(JP4-Pad17)") (class "Default")
      (node (ref "JP4") (pin "17") (pinfunction "17_17") (pintype "passive"))
    )
    (net (code "121") (name "unconnected-(JP4-Pad18)") (class "Default")
      (node (ref "JP4") (pin "18") (pinfunction "18_18") (pintype "passive"))
    )
    (net (code "122") (name "unconnected-(JP4-Pad19)") (class "Default")
      (node (ref "JP4") (pin "19") (pinfunction "19_19") (pintype "passive"))
    )
    (net (code "123") (name "unconnected-(JP4-Pad20)") (class "Default")
      (node (ref "JP4") (pin "20") (pinfunction "20_20") (pintype "passive"))
    )
    (net (code "124") (name "unconnected-(JP4-Pad21)") (class "Default")
      (node (ref "JP4") (pin "21") (pinfunction "21_21") (pintype "passive"))
    )
    (net (code "125") (name "unconnected-(JP4-Pad22)") (class "Default")
      (node (ref "JP4") (pin "22") (pinfunction "22_22") (pintype "passive"))
    )
    (net (code "126") (name "unconnected-(JP4-Pad23)") (class "Default")
      (node (ref "JP4") (pin "23") (pinfunction "23_23") (pintype "passive"))
    )
    (net (code "127") (name "unconnected-(JP4-Pad24)") (class "Default")
      (node (ref "JP4") (pin "24") (pinfunction "24_24") (pintype "passive"))
    )
    (net (code "128") (name "unconnected-(JP4-Pad25)") (class "Default")
      (node (ref "JP4") (pin "25") (pinfunction "25_25") (pintype "passive"))
    )
    (net (code "129") (name "unconnected-(JP4-Pad26)") (class "Default")
      (node (ref "JP4") (pin "26") (pinfunction "26_26") (pintype "passive"))
    )
    (net (code "130") (name "unconnected-(JP4-Pad27)") (class "Default")
      (node (ref "JP4") (pin "27") (pinfunction "27_27") (pintype "passive"))
    )
    (net (code "131") (name "unconnected-(JP4-Pad28)") (class "Default")
      (node (ref "JP4") (pin "28") (pinfunction "28_28") (pintype "passive"))
    )
    (net (code "132") (name "unconnected-(JP4-Pad29)") (class "Default")
      (node (ref "JP4") (pin "29") (pinfunction "29_29") (pintype "passive"))
    )
    (net (code "133") (name "unconnected-(JP4-Pad30)") (class "Default")
      (node (ref "JP4") (pin "30") (pinfunction "30_30") (pintype "passive"))
    )
    (net (code "134") (name "unconnected-(JP4-Pad31)") (class "Default")
      (node (ref "JP4") (pin "31") (pinfunction "31_31") (pintype "passive"))
    )
    (net (code "135") (name "unconnected-(JP4-Pad32)") (class "Default")
      (node (ref "JP4") (pin "32") (pinfunction "32_32") (pintype "passive"))
    )
    (net (code "136") (name "unconnected-(JP9-GRIDEYE-Pad1)") (class "Default")
      (node (ref "JP9-GRIDEYE") (pin "1") (pinfunction "1_1") (pintype "passive"))
    )
    (net (code "137") (name "unconnected-(U1_DHT22-PadNULL)") (class "Default")
      (node (ref "U1_DHT22") (pin "NULL") (pinfunction "NULL_NULL") (pintype "no_connect"))
    )
  )
)
